# untitled_double_sided_AA.net
KiCad netlist of a schematic drawn in EAGLE
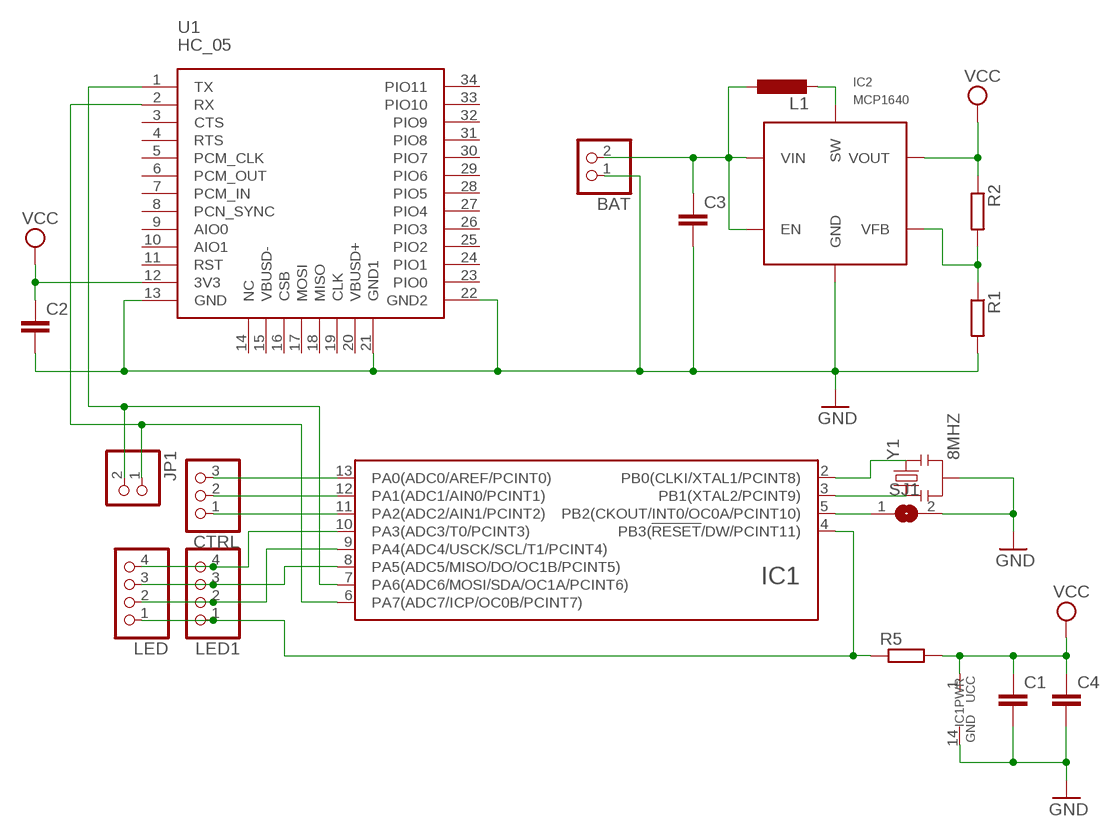
[diagram p0: schematic, sheet 1]

(export (version "E")
  (design (tool "Eeschema 10.0.6"))
  (components
    (comp (ref "BAT")
      (value "PINHD-1X2")
      (footprint "eagle-import:1X02")
      (libsource (lib "eagle-import") (part "PINHD-1X2"))
    )
    (comp (ref "C1")
      (value "C-EUC0805K")
      (footprint "eagle-import:C0805K")
      (libsource (lib "eagle-import") (part "C-EUC0805K"))
    )
    (comp (ref "C2")
      (value "C-EUC0805K")
      (footprint "eagle-import:C0805K")
      (libsource (lib "eagle-import") (part "C-EUC0805K"))
    )
    (comp (ref "C3")
      (value "C-EUC0805K")
      (footprint "eagle-import:C0805K")
      (libsource (lib "eagle-import") (part "C-EUC0805K"))
    )
    (comp (ref "C4")
      (value "C-EUC0805K")
      (footprint "eagle-import:C0805K")
      (libsource (lib "eagle-import") (part "C-EUC0805K"))
    )
    (comp (ref "CTRL")
      (value "PINHD-1X3")
      (footprint "eagle-import:1X03")
      (libsource (lib "eagle-import") (part "PINHD-1X3"))
    )
    (comp (ref "IC1")
      (value "ATTINY24/44/84-SSU")
      (footprint "eagle-import:SOIC14")
      (libsource (lib "eagle-import") (part "ATTINY24/44/84-SSU"))
    )
    (comp (ref "IC2")
      (value "MCP1640")
      (footprint "eagle-import:SOT23-6")
      (libsource (lib "eagle-import") (part "MCP1640"))
    )
    (comp (ref "JP1")
      (value "PINHD-1X2")
      (footprint "eagle-import:1X02")
      (libsource (lib "eagle-import") (part "PINHD-1X2"))
    )
    (comp (ref "L1")
      (value "L-EU0204V")
      (footprint "eagle-import:0204V")
      (libsource (lib "eagle-import") (part "L-EU0204V"))
    )
    (comp (ref "LED")
      (value "PINHD-1X4")
      (footprint "eagle-import:1X04")
      (libsource (lib "eagle-import") (part "PINHD-1X4"))
    )
    (comp (ref "LED1")
      (value "PINHD-1X4")
      (footprint "eagle-import:1X04")
      (libsource (lib "eagle-import") (part "PINHD-1X4"))
    )
    (comp (ref "R1")
      (value "R-EU_M0805")
      (footprint "eagle-import:M0805")
      (libsource (lib "eagle-import") (part "R-EU_M0805"))
    )
    (comp (ref "R2")
      (value "R-EU_M0805")
      (footprint "eagle-import:M0805")
      (libsource (lib "eagle-import") (part "R-EU_M0805"))
    )
    (comp (ref "R5")
      (value "R-EU_M0805")
      (footprint "eagle-import:M0805")
      (libsource (lib "eagle-import") (part "R-EU_M0805"))
    )
    (comp (ref "SJ1") (value "SJ") (footprint "eagle-import:SJ") (libsource (lib "eagle-import") (part "SJ")))
    (comp (ref "U1")
      (value "HC_05")
      (footprint "eagle-import:BLUETOOTH_SMD")
      (libsource (lib "eagle-import") (part "HC_05"))
    )
    (comp (ref "Y1")
      (value "8MHZ")
      (footprint "eagle-import:RESONATOR-SMD")
      (libsource (lib "eagle-import") (part "RESONATOR8MHZ"))
    )
  )
  (nets
    (net (code "1") (name "GND") (class "Default")
      (node (ref "BAT") (pin "1") (pinfunction "1_1") (pintype "passive"))
      (node (ref "C1") (pin "2") (pinfunction "2_2") (pintype "passive"))
      (node (ref "C2") (pin "2") (pinfunction "2_2") (pintype "passive"))
      (node (ref "C3") (pin "2") (pinfunction "2_2") (pintype "passive"))
      (node (ref "C4") (pin "2") (pinfunction "2_2") (pintype "passive"))
      (node (ref "IC1") (pin "14") (pinfunction "GND_14") (pintype "power_in"))
      (node (ref "IC2") (pin "2") (pinfunction "GND_2") (pintype "power_in"))
      (node (ref "R1") (pin "2") (pinfunction "2_2") (pintype "passive"))
      (node (ref "SJ1") (pin "2") (pinfunction "2_2") (pintype "passive"))
      (node (ref "U1") (pin "13") (pinfunction "GND_13") (pintype "bidirectional"))
      (node (ref "U1") (pin "21") (pinfunction "GND1_21") (pintype "bidirectional"))
      (node (ref "U1") (pin "22") (pinfunction "GND2_22") (pintype "bidirectional"))
      (node (ref "Y1") (pin "2") (pinfunction "2_2") (pintype "passive"))
    )
    (net (code "2") (name "Net-(IC1A-PA0(ADC0{slash}AREF{slash}PCINT0))") (class "Default")
      (node (ref "CTRL") (pin "3") (pinfunction "3_3") (pintype "passive"))
      (node (ref "IC1") (pin "13") (pinfunction "PA0(ADC0/AREF/PCINT0)_13") (pintype "bidirectional"))
    )
    (net (code "3") (name "Net-(IC1A-PA1(ADC1{slash}AIN0{slash}PCINT1))") (class "Default")
      (node (ref "CTRL") (pin "2") (pinfunction "2_2") (pintype "passive"))
      (node (ref "IC1") (pin "12") (pinfunction "PA1(ADC1/AIN0/PCINT1)_12") (pintype "bidirectional"))
    )
    (net (code "4") (name "Net-(IC1A-PA2(ADC2{slash}AIN1{slash}PCINT2))") (class "Default")
      (node (ref "CTRL") (pin "1") (pinfunction "1_1") (pintype "passive"))
      (node (ref "IC1") (pin "11") (pinfunction "PA2(ADC2/AIN1/PCINT2)_11") (pintype "bidirectional"))
    )
    (net (code "5") (name "Net-(IC1A-PA3(ADC3{slash}T0{slash}PCINT3))") (class "Default")
      (node (ref "IC1") (pin "10") (pinfunction "PA3(ADC3/T0/PCINT3)_10") (pintype "bidirectional"))
      (node (ref "LED") (pin "4") (pinfunction "4_4") (pintype "passive"))
      (node (ref "LED1") (pin "4") (pinfunction "4_4") (pintype "passive"))
    )
    (net (code "6") (name "Net-(IC1A-PA4(ADC4{slash}USCK{slash}SCL{slash}T1{slash}PCINT4))") (class "Default")
      (node (ref "IC1") (pin "9") (pinfunction "PA4(ADC4/USCK/SCL/T1/PCINT4)_9") (pintype "bidirectional"))
      (node (ref "LED") (pin "2") (pinfunction "2_2") (pintype "passive"))
      (node (ref "LED1") (pin "2") (pinfunction "2_2") (pintype "passive"))
    )
    (net (code "7") (name "Net-(IC1A-PA5(ADC5{slash}MISO{slash}DO{slash}OC1B{slash}PCINT5))") (class "Default")
      (node (ref "IC1") (pin "8") (pinfunction "PA5(ADC5/MISO/DO/OC1B/PCINT5)_8") (pintype "bidirectional"))
      (node (ref "LED") (pin "3") (pinfunction "3_3") (pintype "passive"))
      (node (ref "LED1") (pin "3") (pinfunction "3_3") (pintype "passive"))
    )
    (net (code "8") (name "Net-(IC1A-PA6(ADC6{slash}MOSI{slash}SDA{slash}OC1A{slash}PCINT6))") (class "Default")
      (node (ref "IC1") (pin "7") (pinfunction "PA6(ADC6/MOSI/SDA/OC1A/PCINT6)_7") (pintype "bidirectional"))
      (node (ref "JP1") (pin "2") (pinfunction "2_2") (pintype "passive"))
      (node (ref "U1") (pin "1") (pinfunction "TX_1") (pintype "bidirectional"))
    )
    (net (code "9") (name "Net-(IC1A-PA7(ADC7{slash}ICP{slash}OC0B{slash}PCINT7))") (class "Default")
      (node (ref "IC1") (pin "6") (pinfunction "PA7(ADC7/ICP/OC0B/PCINT7)_6") (pintype "bidirectional"))
      (node (ref "JP1") (pin "1") (pinfunction "1_1") (pintype "passive"))
      (node (ref "U1") (pin "2") (pinfunction "RX_2") (pintype "bidirectional"))
    )
    (net (code "10") (name "Net-(IC1A-PB0(CLKI{slash}XTAL1{slash}PCINT8))") (class "Default")
      (node (ref "IC1") (pin "2") (pinfunction "PB0(CLKI/XTAL1/PCINT8)_2") (pintype "bidirectional"))
      (node (ref "Y1") (pin "3") (pinfunction "3_3") (pintype "passive"))
    )
    (net (code "11") (name "Net-(IC1A-PB1(XTAL2{slash}PCINT9))") (class "Default")
      (node (ref "IC1") (pin "3") (pinfunction "PB1(XTAL2/PCINT9)_3") (pintype "bidirectional"))
      (node (ref "Y1") (pin "1") (pinfunction "1_1") (pintype "passive"))
    )
    (net (code "12") (name "Net-(IC1A-PB2(CKOUT{slash}INT0{slash}OC0A{slash}PCINT10))") (class "Default")
      (node (ref "IC1") (pin "5") (pinfunction "PB2(CKOUT/INT0/OC0A/PCINT10)_5") (pintype "bidirectional"))
      (node (ref "SJ1") (pin "1") (pinfunction "1_1") (pintype "passive"))
    )
    (net (code "13") (name "Net-(IC1A-PB3(~{RESET}{slash}DW{slash}PCINT11))") (class "Default")
      (node (ref "IC1") (pin "4") (pinfunction "PB3(~{RESET}/DW/PCINT11)_4") (pintype "bidirectional"))
      (node (ref "LED") (pin "1") (pinfunction "1_1") (pintype "passive"))
      (node (ref "LED1") (pin "1") (pinfunction "1_1") (pintype "passive"))
      (node (ref "R5") (pin "1") (pinfunction "1_1") (pintype "passive"))
    )
    (net (code "14") (name "Net-(IC2-EN)") (class "Default")
      (node (ref "BAT") (pin "2") (pinfunction "2_2") (pintype "passive"))
      (node (ref "C3") (pin "1") (pinfunction "1_1") (pintype "passive"))
      (node (ref "IC2") (pin "3") (pinfunction "EN_3") (pintype "input"))
      (node (ref "IC2") (pin "6") (pinfunction "VIN_6") (pintype "input"))
      (node (ref "L1") (pin "1") (pinfunction "1_1") (pintype "passive"))
    )
    (net (code "15") (name "Net-(IC2-SW)") (class "Default")
      (node (ref "IC2") (pin "1") (pinfunction "SW_1") (pintype "passive"))
      (node (ref "L1") (pin "2") (pinfunction "2_2") (pintype "passive"))
    )
    (net (code "16") (name "Net-(IC2-VFB)") (class "Default")
      (node (ref "IC2") (pin "4") (pinfunction "VFB_4") (pintype "input"))
      (node (ref "R1") (pin "1") (pinfunction "1_1") (pintype "passive"))
      (node (ref "R2") (pin "2") (pinfunction "2_2") (pintype "passive"))
    )
    (net (code "17") (name "VCC") (class "Default")
      (node (ref "C1") (pin "1") (pinfunction "1_1") (pintype "passive"))
      (node (ref "C2") (pin "1") (pinfunction "1_1") (pintype "passive"))
      (node (ref "C4") (pin "1") (pinfunction "1_1") (pintype "passive"))
      (node (ref "IC1") (pin "1") (pinfunction "UCC_1") (pintype "power_in"))
      (node (ref "IC2") (pin "5") (pinfunction "VOUT_5") (pintype "power_in"))
      (node (ref "R2") (pin "1") (pinfunction "1_1") (pintype "passive"))
      (node (ref "R5") (pin "2") (pinfunction "2_2") (pintype "passive"))
      (node (ref "U1") (pin "12") (pinfunction "3V3_12") (pintype "bidirectional"))
    )
    (net (code "18") (name "unconnected-(U1-AIO0-Pad9)") (class "Default")
      (node (ref "U1") (pin "9") (pinfunction "AIO0_9") (pintype "bidirectional"))
    )
    (net (code "19") (name "unconnected-(U1-AIO1-Pad10)") (class "Default")
      (node (ref "U1") (pin "10") (pinfunction "AIO1_10") (pintype "bidirectional"))
    )
    (net (code "20") (name "unconnected-(U1-CLK-Pad19)") (class "Default")
      (node (ref "U1") (pin "19") (pinfunction "CLK_19") (pintype "bidirectional"))
    )
    (net (code "21") (name "unconnected-(U1-CSB-Pad16)") (class "Default")
      (node (ref "U1") (pin "16") (pinfunction "CSB_16") (pintype "bidirectional"))
    )
    (net (code "22") (name "unconnected-(U1-CTS-Pad3)") (class "Default")
      (node (ref "U1") (pin "3") (pinfunction "CTS_3") (pintype "bidirectional"))
    )
    (net (code "23") (name "unconnected-(U1-MISO-Pad18)") (class "Default")
      (node (ref "U1") (pin "18") (pinfunction "MISO_18") (pintype "bidirectional"))
    )
    (net (code "24") (name "unconnected-(U1-MOSI-Pad17)") (class "Default")
      (node (ref "U1") (pin "17") (pinfunction "MOSI_17") (pintype "bidirectional"))
    )
    (net (code "25") (name "unconnected-(U1-NC-Pad14)") (class "Default")
      (node (ref "U1") (pin "14") (pinfunction "NC_14") (pintype "bidirectional"))
    )
    (net (code "26") (name "unconnected-(U1-PCM_CLK-Pad5)") (class "Default")
      (node (ref "U1") (pin "5") (pinfunction "PCM_CLK_5") (pintype "bidirectional"))
    )
    (net (code "27") (name "unconnected-(U1-PCM_IN-Pad7)") (class "Default")
      (node (ref "U1") (pin "7") (pinfunction "PCM_IN_7") (pintype "bidirectional"))
    )
    (net (code "28") (name "unconnected-(U1-PCM_OUT-Pad6)") (class "Default")
      (node (ref "U1") (pin "6") (pinfunction "PCM_OUT_6") (pintype "bidirectional"))
    )
    (net (code "29") (name "unconnected-(U1-PCN_SYNC-Pad8)") (class "Default")
      (node (ref "U1") (pin "8") (pinfunction "PCN_SYNC_8") (pintype "bidirectional"))
    )
    (net (code "30") (name "unconnected-(U1-PIO0-Pad23)") (class "Default")
      (node (ref "U1") (pin "23") (pinfunction "PIO0_23") (pintype "bidirectional"))
    )
    (net (code "31") (name "unconnected-(U1-PIO1-Pad24)") (class "Default")
      (node (ref "U1") (pin "24") (pinfunction "PIO1_24") (pintype "bidirectional"))
    )
    (net (code "32") (name "unconnected-(U1-PIO2-Pad25)") (class "Default")
      (node (ref "U1") (pin "25") (pinfunction "PIO2_25") (pintype "bidirectional"))
    )
    (net (code "33") (name "unconnected-(U1-PIO3-Pad26)") (class "Default")
      (node (ref "U1") (pin "26") (pinfunction "PIO3_26") (pintype "bidirectional"))
    )
    (net (code "34") (name "unconnected-(U1-PIO4-Pad27)") (class "Default")
      (node (ref "U1") (pin "27") (pinfunction "PIO4_27") (pintype "bidirectional"))
    )
    (net (code "35") (name "unconnected-(U1-PIO5-Pad28)") (class "Default")
      (node (ref "U1") (pin "28") (pinfunction "PIO5_28") (pintype "bidirectional"))
    )
    (net (code "36") (name "unconnected-(U1-PIO6-Pad29)") (class "Default")
      (node (ref "U1") (pin "29") (pinfunction "PIO6_29") (pintype "bidirectional"))
    )
    (net (code "37") (name "unconnected-(U1-PIO7-Pad30)") (class "Default")
      (node (ref "U1") (pin "30") (pinfunction "PIO7_30") (pintype "bidirectional"))
    )
    (net (code "38") (name "unconnected-(U1-PIO8-Pad31)") (class "Default")
      (node (ref "U1") (pin "31") (pinfunction "PIO8_31") (pintype "bidirectional"))
    )
    (net (code "39") (name "unconnected-(U1-PIO9-Pad32)") (class "Default")
      (node (ref "U1") (pin "32") (pinfunction "PIO9_32") (pintype "bidirectional"))
    )
    (net (code "40") (name "unconnected-(U1-PIO10-Pad33)") (class "Default")
      (node (ref "U1") (pin "33") (pinfunction "PIO10_33") (pintype "bidirectional"))
    )
    (net (code "41") (name "unconnected-(U1-PIO11-Pad34)") (class "Default")
      (node (ref "U1") (pin "34") (pinfunction "PIO11_34") (pintype "bidirectional"))
    )
    (net (code "42") (name "unconnected-(U1-RST-Pad11)") (class "Default")
      (node (ref "U1") (pin "11") (pinfunction "RST_11") (pintype "bidirectional"))
    )
    (net (code "43") (name "unconnected-(U1-RTS-Pad4)") (class "Default")
      (node (ref "U1") (pin "4") (pinfunction "RTS_4") (pintype "bidirectional"))
    )
    (net (code "44") (name "unconnected-(U1-VBUSD+-Pad20)") (class "Default")
      (node (ref "U1") (pin "20") (pinfunction "VBUSD+_20") (pintype "bidirectional"))
    )
    (net (code "45") (name "unconnected-(U1-VBUSD--Pad15)") (class "Default")
      (node (ref "U1") (pin "15") (pinfunction "VBUSD-_15") (pintype "bidirectional"))
    )
  )
)
